# Uart_Can.net
KiCad netlist of a schematic drawn in Altium Designer
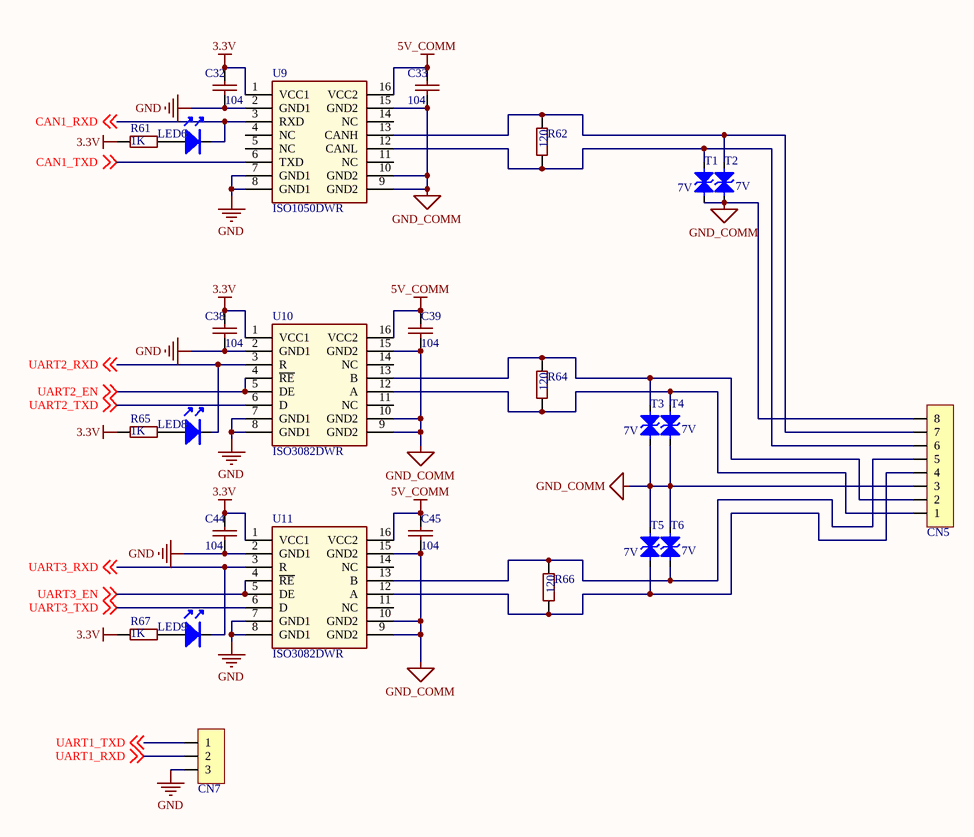
[diagram p0: Uart_Can.SchDoc]

(export (version "E")
  (design (tool "Eeschema 10.0.6"))
  (components
    (comp (ref "C32")
      (value "104")
      (footprint "0805SMD_Cap")
      (description "贴片电容")
      (libsource (lib "ST_GND_Sch") (part "SMD_Cap"))
    )
    (comp (ref "C33")
      (value "104")
      (footprint "0805SMD_Cap")
      (description "贴片电容")
      (libsource (lib "ST_GND_Sch") (part "SMD_Cap"))
    )
    (comp (ref "C38")
      (value "104")
      (footprint "0805SMD_Cap")
      (description "贴片电容")
      (libsource (lib "ST_GND_Sch") (part "SMD_Cap"))
    )
    (comp (ref "C39")
      (value "104")
      (footprint "0805SMD_Cap")
      (description "贴片电容")
      (libsource (lib "ST_GND_Sch") (part "SMD_Cap"))
    )
    (comp (ref "C44")
      (value "104")
      (footprint "0805SMD_Cap")
      (description "贴片电容")
      (libsource (lib "ST_GND_Sch") (part "SMD_Cap"))
    )
    (comp (ref "C45")
      (value "104")
      (footprint "0805SMD_Cap")
      (description "贴片电容")
      (libsource (lib "ST_GND_Sch") (part "SMD_Cap"))
    )
    (comp (ref "CN5")
      (value "CON8")
      (footprint "WJ15EDGRM-3.81-8P")
      (description "连接器")
      (libsource (lib "ST_GND_Sch") (part "CON8"))
    )
    (comp (ref "CN7")
      (value "CON3")
      (footprint "DIP3")
      (description "连接器")
      (libsource (lib "ST_GND_Sch") (part "CON3"))
    )
    (comp (ref "LED6")
      (value "LED")
      (footprint "发光二极管0805")
      (description "发光二极管")
      (libsource (lib "ST_GND_Sch") (part "LED"))
    )
    (comp (ref "LED8")
      (value "LED")
      (footprint "发光二极管0805")
      (description "发光二极管")
      (libsource (lib "ST_GND_Sch") (part "LED"))
    )
    (comp (ref "LED9")
      (value "LED")
      (footprint "发光二极管0805")
      (description "发光二极管")
      (libsource (lib "ST_GND_Sch") (part "LED"))
    )
    (comp (ref "R61")
      (value "1K")
      (footprint "0805_SMD_R")
      (description "贴片电阻")
      (libsource (lib "ST_GND_Sch") (part "SMD_0805"))
    )
    (comp (ref "R62")
      (value "120")
      (footprint "0805_SMD_R")
      (description "贴片电阻")
      (libsource (lib "") (part "SMD_0805_1"))
    )
    (comp (ref "R64")
      (value "120")
      (footprint "0805_SMD_R")
      (description "贴片电阻")
      (libsource (lib "") (part "SMD_0805_1"))
    )
    (comp (ref "R65")
      (value "1K")
      (footprint "0805_SMD_R")
      (description "贴片电阻")
      (libsource (lib "ST_GND_Sch") (part "SMD_0805"))
    )
    (comp (ref "R66")
      (value "120")
      (footprint "0805_SMD_R")
      (description "贴片电阻")
      (libsource (lib "") (part "SMD_0805_1"))
    )
    (comp (ref "R67")
      (value "1K")
      (footprint "0805_SMD_R")
      (description "贴片电阻")
      (libsource (lib "ST_GND_Sch") (part "SMD_0805"))
    )
    (comp (ref "T1")
      (value "7V")
      (footprint "二极管SMA")
      (description "双向TVS_?V(SMA)")
      (libsource (lib "ST_GND_Sch") (part "双向TVS_?V(SMA)"))
    )
    (comp (ref "T2")
      (value "7V")
      (footprint "二极管SMA")
      (description "双向TVS_?V(SMA)")
      (libsource (lib "ST_GND_Sch") (part "双向TVS_?V(SMA)"))
    )
    (comp (ref "T3")
      (value "7V")
      (footprint "二极管SMA")
      (description "双向TVS_?V(SMA)")
      (libsource (lib "ST_GND_Sch") (part "双向TVS_?V(SMA)"))
    )
    (comp (ref "T4")
      (value "7V")
      (footprint "二极管SMA")
      (description "双向TVS_?V(SMA)")
      (libsource (lib "ST_GND_Sch") (part "双向TVS_?V(SMA)"))
    )
    (comp (ref "T5")
      (value "7V")
      (footprint "二极管SMA")
      (description "双向TVS_?V(SMA)")
      (libsource (lib "ST_GND_Sch") (part "双向TVS_?V(SMA)"))
    )
    (comp (ref "T6")
      (value "7V")
      (footprint "二极管SMA")
      (description "双向TVS_?V(SMA)")
      (libsource (lib "ST_GND_Sch") (part "双向TVS_?V(SMA)"))
    )
    (comp (ref "U9")
      (value "ISO1050DWR")
      (footprint "SOIC_16")
      (description "CAN隔离芯片")
      (libsource (lib "ST_GND_Sch") (part "ISO1050DWR"))
    )
    (comp (ref "U10")
      (value "ISO3082DWR")
      (footprint "SOIC_16")
      (description "485隔离芯片")
      (libsource (lib "ST_GND_Sch") (part "ISO3082DWR"))
    )
    (comp (ref "U11")
      (value "ISO3082DWR")
      (footprint "SOIC_16")
      (description "485隔离芯片")
      (libsource (lib "ST_GND_Sch") (part "ISO3082DWR"))
    )
  )
  (nets
    (net (code "1") (name "3.3V") (class "Default")
      (node (ref "C32") (pin "2") (pintype "passive"))
      (node (ref "C38") (pin "2") (pintype "passive"))
      (node (ref "C44") (pin "2") (pintype "passive"))
      (node (ref "R61") (pin "2") (pinfunction "2_2") (pintype "passive"))
      (node (ref "R65") (pin "2") (pinfunction "2_2") (pintype "passive"))
      (node (ref "R67") (pin "2") (pinfunction "2_2") (pintype "passive"))
      (node (ref "U10") (pin "1") (pinfunction "VCC1_1") (pintype "passive"))
      (node (ref "U11") (pin "1") (pinfunction "VCC1_1") (pintype "passive"))
      (node (ref "U9") (pin "1") (pinfunction "VCC1_1") (pintype "passive"))
    )
    (net (code "2") (name "5V_COMM") (class "Default")
      (node (ref "C33") (pin "2") (pintype "passive"))
      (node (ref "C39") (pin "2") (pintype "passive"))
      (node (ref "C45") (pin "2") (pintype "passive"))
      (node (ref "U10") (pin "16") (pinfunction "VCC2_16") (pintype "passive"))
      (node (ref "U11") (pin "16") (pinfunction "VCC2_16") (pintype "passive"))
      (node (ref "U9") (pin "16") (pinfunction "VCC2_16") (pintype "passive"))
    )
    (net (code "3") (name "CAN1_RXD") (class "Default")
      (node (ref "LED6") (pin "K") (pintype "passive"))
      (node (ref "U9") (pin "3") (pinfunction "RXD_3") (pintype "passive"))
    )
    (net (code "4") (name "CAN1_TXD") (class "Default")
      (node (ref "U9") (pin "6") (pinfunction "TXD_6") (pintype "passive"))
    )
    (net (code "5") (name "GND") (class "Default")
      (node (ref "C32") (pin "1") (pintype "passive"))
      (node (ref "C38") (pin "1") (pintype "passive"))
      (node (ref "C44") (pin "1") (pintype "passive"))
      (node (ref "CN7") (pin "3") (pinfunction "3_3") (pintype "passive"))
      (node (ref "U10") (pin "2") (pinfunction "GND1_2") (pintype "passive"))
      (node (ref "U10") (pin "7") (pinfunction "GND1_7") (pintype "passive"))
      (node (ref "U10") (pin "8") (pinfunction "GND1_8") (pintype "passive"))
      (node (ref "U11") (pin "2") (pinfunction "GND1_2") (pintype "passive"))
      (node (ref "U11") (pin "7") (pinfunction "GND1_7") (pintype "passive"))
      (node (ref "U11") (pin "8") (pinfunction "GND1_8") (pintype "passive"))
      (node (ref "U9") (pin "2") (pinfunction "GND1_2") (pintype "passive"))
      (node (ref "U9") (pin "7") (pinfunction "GND1_7") (pintype "passive"))
      (node (ref "U9") (pin "8") (pinfunction "GND1_8") (pintype "passive"))
    )
    (net (code "6") (name "GND_COMM") (class "Default")
      (node (ref "C33") (pin "1") (pintype "passive"))
      (node (ref "C39") (pin "1") (pintype "passive"))
      (node (ref "C45") (pin "1") (pintype "passive"))
      (node (ref "CN5") (pin "3") (pinfunction "3_3") (pintype "passive"))
      (node (ref "CN5") (pin "8") (pinfunction "8_8") (pintype "passive"))
      (node (ref "T1") (pin "A") (pinfunction "A_A") (pintype "passive"))
      (node (ref "T2") (pin "A") (pinfunction "A_A") (pintype "passive"))
      (node (ref "T3") (pin "A") (pinfunction "A_A") (pintype "passive"))
      (node (ref "T4") (pin "A") (pinfunction "A_A") (pintype "passive"))
      (node (ref "T5") (pin "K") (pinfunction "K_K") (pintype "passive"))
      (node (ref "T6") (pin "K") (pinfunction "K_K") (pintype "passive"))
      (node (ref "U10") (pin "10") (pinfunction "GND2_10") (pintype "passive"))
      (node (ref "U10") (pin "15") (pinfunction "GND2_15") (pintype "passive"))
      (node (ref "U10") (pin "9") (pinfunction "GND2_9") (pintype "passive"))
      (node (ref "U11") (pin "10") (pinfunction "GND2_10") (pintype "passive"))
      (node (ref "U11") (pin "15") (pinfunction "GND2_15") (pintype "passive"))
      (node (ref "U11") (pin "9") (pinfunction "GND2_9") (pintype "passive"))
      (node (ref "U9") (pin "10") (pinfunction "GND2_10") (pintype "passive"))
      (node (ref "U9") (pin "15") (pinfunction "GND2_15") (pintype "passive"))
      (node (ref "U9") (pin "9") (pinfunction "GND2_9") (pintype "passive"))
    )
    (net (code "7") (name "Net-(LED6-PadA)") (class "Default")
      (node (ref "LED6") (pin "A") (pintype "passive"))
      (node (ref "R61") (pin "1") (pinfunction "1_1") (pintype "passive"))
    )
    (net (code "8") (name "Net-(LED8-PadA)") (class "Default")
      (node (ref "LED8") (pin "A") (pintype "passive"))
      (node (ref "R65") (pin "1") (pinfunction "1_1") (pintype "passive"))
    )
    (net (code "9") (name "Net-(LED9-PadA)") (class "Default")
      (node (ref "LED9") (pin "A") (pintype "passive"))
      (node (ref "R67") (pin "1") (pinfunction "1_1") (pintype "passive"))
    )
    (net (code "10") (name "Net-(U9-CANH)") (class "Default")
      (node (ref "CN5") (pin "7") (pinfunction "7_7") (pintype "passive"))
      (node (ref "R62") (pin "2") (pinfunction "2_2") (pintype "passive"))
      (node (ref "T2") (pin "K") (pinfunction "K_K") (pintype "passive"))
      (node (ref "U9") (pin "13") (pinfunction "CANH_13") (pintype "passive"))
    )
    (net (code "11") (name "Net-(U9-CANL)") (class "Default")
      (node (ref "CN5") (pin "6") (pinfunction "6_6") (pintype "passive"))
      (node (ref "R62") (pin "1") (pinfunction "1_1") (pintype "passive"))
      (node (ref "T1") (pin "K") (pinfunction "K_K") (pintype "passive"))
      (node (ref "U9") (pin "12") (pinfunction "CANL_12") (pintype "passive"))
    )
    (net (code "12") (name "Net-(U10-A)") (class "Default")
      (node (ref "CN5") (pin "1") (pinfunction "1_1") (pintype "passive"))
      (node (ref "R64") (pin "1") (pinfunction "1_1") (pintype "passive"))
      (node (ref "T4") (pin "K") (pinfunction "K_K") (pintype "passive"))
      (node (ref "U10") (pin "12") (pinfunction "A_12") (pintype "passive"))
    )
    (net (code "13") (name "Net-(U10-B)") (class "Default")
      (node (ref "CN5") (pin "2") (pinfunction "2_2") (pintype "passive"))
      (node (ref "R64") (pin "2") (pinfunction "2_2") (pintype "passive"))
      (node (ref "T3") (pin "K") (pinfunction "K_K") (pintype "passive"))
      (node (ref "U10") (pin "13") (pinfunction "B_13") (pintype "passive"))
    )
    (net (code "14") (name "Net-(U11-A)") (class "Default")
      (node (ref "CN5") (pin "4") (pinfunction "4_4") (pintype "passive"))
      (node (ref "R66") (pin "1") (pinfunction "1_1") (pintype "passive"))
      (node (ref "T5") (pin "A") (pinfunction "A_A") (pintype "passive"))
      (node (ref "U11") (pin "12") (pinfunction "A_12") (pintype "passive"))
    )
    (net (code "15") (name "Net-(U11-B)") (class "Default")
      (node (ref "CN5") (pin "5") (pinfunction "5_5") (pintype "passive"))
      (node (ref "R66") (pin "2") (pinfunction "2_2") (pintype "passive"))
      (node (ref "T6") (pin "A") (pinfunction "A_A") (pintype "passive"))
      (node (ref "U11") (pin "13") (pinfunction "B_13") (pintype "passive"))
    )
    (net (code "16") (name "UART1_RXD") (class "Default")
      (node (ref "CN7") (pin "2") (pinfunction "2_2") (pintype "passive"))
    )
    (net (code "17") (name "UART1_TXD") (class "Default")
      (node (ref "CN7") (pin "1") (pinfunction "1_1") (pintype "passive"))
    )
    (net (code "18") (name "UART2_EN") (class "Default")
      (node (ref "U10") (pin "4") (pinfunction "~{RE}_4") (pintype "passive"))
      (node (ref "U10") (pin "5") (pinfunction "DE_5") (pintype "passive"))
    )
    (net (code "19") (name "UART2_RXD") (class "Default")
      (node (ref "LED8") (pin "K") (pintype "passive"))
      (node (ref "U10") (pin "3") (pinfunction "R_3") (pintype "passive"))
    )
    (net (code "20") (name "UART2_TXD") (class "Default")
      (node (ref "U10") (pin "6") (pinfunction "D_6") (pintype "passive"))
    )
    (net (code "21") (name "UART3_EN") (class "Default")
      (node (ref "U11") (pin "4") (pinfunction "~{RE}_4") (pintype "passive"))
      (node (ref "U11") (pin "5") (pinfunction "DE_5") (pintype "passive"))
    )
    (net (code "22") (name "UART3_RXD") (class "Default")
      (node (ref "LED9") (pin "K") (pintype "passive"))
      (node (ref "U11") (pin "3") (pinfunction "R_3") (pintype "passive"))
    )
    (net (code "23") (name "UART3_TXD") (class "Default")
      (node (ref "U11") (pin "6") (pinfunction "D_6") (pintype "passive"))
    )
    (net (code "24") (name "unconnected-(U9-NC-Pad4)") (class "Default")
      (node (ref "U9") (pin "4") (pinfunction "NC_4") (pintype "passive"))
    )
    (net (code "25") (name "unconnected-(U9-NC-Pad5)") (class "Default")
      (node (ref "U9") (pin "5") (pinfunction "NC_5") (pintype "passive"))
    )
    (net (code "26") (name "unconnected-(U9-NC-Pad11)") (class "Default")
      (node (ref "U9") (pin "11") (pinfunction "NC_11") (pintype "passive"))
    )
    (net (code "27") (name "unconnected-(U9-NC-Pad14)") (class "Default")
      (node (ref "U9") (pin "14") (pinfunction "NC_14") (pintype "passive"))
    )
    (net (code "28") (name "unconnected-(U10-NC-Pad11)") (class "Default")
      (node (ref "U10") (pin "11") (pinfunction "NC_11") (pintype "passive"))
    )
    (net (code "29") (name "unconnected-(U10-NC-Pad14)") (class "Default")
      (node (ref "U10") (pin "14") (pinfunction "NC_14") (pintype "passive"))
    )
    (net (code "30") (name "unconnected-(U11-NC-Pad11)") (class "Default")
      (node (ref "U11") (pin "11") (pinfunction "NC_11") (pintype "passive"))
    )
    (net (code "31") (name "unconnected-(U11-NC-Pad14)") (class "Default")
      (node (ref "U11") (pin "14") (pinfunction "NC_14") (pintype "passive"))
    )
  )
)
